# slave_interface.net
KiCad netlist of a schematic drawn in Altium Designer
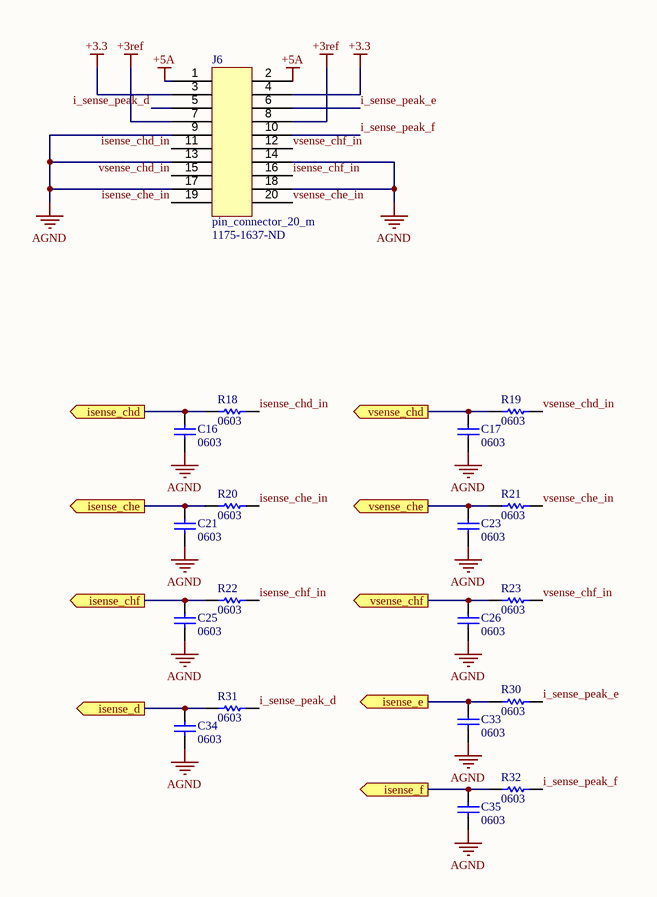
[diagram p0: slave_interface.SchDoc]

(export (version "E")
  (design (tool "Eeschema 10.0.6"))
  (components
    (comp (ref "C16")
      (value "0603")
      (footprint "CAP 0603_1608")
      (description "Capacitor")
      (fields (field (name "PUBLISHER") "Altium Limited"))
      (libsource (lib "Miscellaneous Devices") (part "Cap"))
    )
    (comp (ref "C17")
      (value "0603")
      (footprint "CAP 0603_1608")
      (description "Capacitor")
      (fields (field (name "PUBLISHER") "Altium Limited"))
      (libsource (lib "Miscellaneous Devices") (part "Cap"))
    )
    (comp (ref "C21")
      (value "0603")
      (footprint "CAP 0603_1608")
      (description "Capacitor")
      (fields (field (name "PUBLISHER") "Altium Limited"))
      (libsource (lib "Miscellaneous Devices") (part "Cap"))
    )
    (comp (ref "C23")
      (value "0603")
      (footprint "CAP 0603_1608")
      (description "Capacitor")
      (fields (field (name "PUBLISHER") "Altium Limited"))
      (libsource (lib "Miscellaneous Devices") (part "Cap"))
    )
    (comp (ref "C25")
      (value "0603")
      (footprint "CAP 0603_1608")
      (description "Capacitor")
      (fields (field (name "PUBLISHER") "Altium Limited"))
      (libsource (lib "Miscellaneous Devices") (part "Cap"))
    )
    (comp (ref "C26")
      (value "0603")
      (footprint "CAP 0603_1608")
      (description "Capacitor")
      (fields (field (name "PUBLISHER") "Altium Limited"))
      (libsource (lib "Miscellaneous Devices") (part "Cap"))
    )
    (comp (ref "C33")
      (value "0603")
      (footprint "CAP 0603_1608")
      (description "Capacitor")
      (fields (field (name "PUBLISHER") "Altium Limited"))
      (libsource (lib "Miscellaneous Devices") (part "Cap"))
    )
    (comp (ref "C34")
      (value "0603")
      (footprint "CAP 0603_1608")
      (description "Capacitor")
      (fields (field (name "PUBLISHER") "Altium Limited"))
      (libsource (lib "Miscellaneous Devices") (part "Cap"))
    )
    (comp (ref "C35")
      (value "0603")
      (footprint "CAP 0603_1608")
      (description "Capacitor")
      (fields (field (name "PUBLISHER") "Altium Limited"))
      (libsource (lib "Miscellaneous Devices") (part "Cap"))
    )
    (comp (ref "J6")
      (value "pin_connector_20_m")
      (footprint "PIN_20_MALE_3220-20-0300-00")
      (fields (field (name "SUPPLIER PART NUMBER 1") "1175-1637-ND"))
      (libsource (lib "coil_driver_lib") (part "pin_connector_20_m"))
    )
    (comp (ref "R18")
      (value "0603")
      (footprint "RES 0603_1608")
      (description "Resistor")
      (fields (field (name "PUBLISHER") "Altium Limited"))
      (libsource (lib "Miscellaneous Devices") (part "Res1"))
    )
    (comp (ref "R19")
      (value "0603")
      (footprint "RES 0603_1608")
      (description "Resistor")
      (fields (field (name "PUBLISHER") "Altium Limited"))
      (libsource (lib "Miscellaneous Devices") (part "Res1"))
    )
    (comp (ref "R20")
      (value "0603")
      (footprint "RES 0603_1608")
      (description "Resistor")
      (fields (field (name "PUBLISHER") "Altium Limited"))
      (libsource (lib "Miscellaneous Devices") (part "Res1"))
    )
    (comp (ref "R21")
      (value "0603")
      (footprint "RES 0603_1608")
      (description "Resistor")
      (fields (field (name "PUBLISHER") "Altium Limited"))
      (libsource (lib "Miscellaneous Devices") (part "Res1"))
    )
    (comp (ref "R22")
      (value "0603")
      (footprint "RES 0603_1608")
      (description "Resistor")
      (fields (field (name "PUBLISHER") "Altium Limited"))
      (libsource (lib "Miscellaneous Devices") (part "Res1"))
    )
    (comp (ref "R23")
      (value "0603")
      (footprint "RES 0603_1608")
      (description "Resistor")
      (fields (field (name "PUBLISHER") "Altium Limited"))
      (libsource (lib "Miscellaneous Devices") (part "Res1"))
    )
    (comp (ref "R30")
      (value "0603")
      (footprint "RES 0603_1608")
      (description "Resistor")
      (fields (field (name "PUBLISHER") "Altium Limited"))
      (libsource (lib "Miscellaneous Devices") (part "Res1"))
    )
    (comp (ref "R31")
      (value "0603")
      (footprint "RES 0603_1608")
      (description "Resistor")
      (fields (field (name "PUBLISHER") "Altium Limited"))
      (libsource (lib "Miscellaneous Devices") (part "Res1"))
    )
    (comp (ref "R32")
      (value "0603")
      (footprint "RES 0603_1608")
      (description "Resistor")
      (fields (field (name "PUBLISHER") "Altium Limited"))
      (libsource (lib "Miscellaneous Devices") (part "Res1"))
    )
  )
  (nets
    (net (code "1") (name "+3.3") (class "Default")
      (node (ref "J6") (pin "3") (pintype "passive"))
      (node (ref "J6") (pin "4") (pintype "passive"))
    )
    (net (code "2") (name "+3ref") (class "Default")
      (node (ref "J6") (pin "7") (pintype "passive"))
      (node (ref "J6") (pin "8") (pintype "passive"))
    )
    (net (code "3") (name "+5A") (class "Default")
      (node (ref "J6") (pin "1") (pintype "passive"))
      (node (ref "J6") (pin "2") (pintype "passive"))
    )
    (net (code "4") (name "/i_sense_peak_d") (class "Default")
      (node (ref "J6") (pin "5") (pintype "passive"))
      (node (ref "R31") (pin "2") (pinfunction "2_2") (pintype "passive"))
    )
    (net (code "5") (name "/i_sense_peak_e") (class "Default")
      (node (ref "J6") (pin "6") (pintype "passive"))
      (node (ref "R30") (pin "2") (pinfunction "2_2") (pintype "passive"))
    )
    (net (code "6") (name "/i_sense_peak_f") (class "Default")
      (node (ref "J6") (pin "10") (pintype "passive"))
      (node (ref "R32") (pin "2") (pinfunction "2_2") (pintype "passive"))
    )
    (net (code "7") (name "/isense_chd") (class "Default")
      (node (ref "C16") (pin "2") (pinfunction "2_2") (pintype "passive"))
      (node (ref "R18") (pin "1") (pinfunction "1_1") (pintype "passive"))
    )
    (net (code "8") (name "/isense_chd_in") (class "Default")
      (node (ref "J6") (pin "11") (pintype "passive"))
      (node (ref "R18") (pin "2") (pinfunction "2_2") (pintype "passive"))
    )
    (net (code "9") (name "/isense_che") (class "Default")
      (node (ref "C21") (pin "2") (pinfunction "2_2") (pintype "passive"))
      (node (ref "R20") (pin "1") (pinfunction "1_1") (pintype "passive"))
    )
    (net (code "10") (name "/isense_che_in") (class "Default")
      (node (ref "J6") (pin "19") (pintype "passive"))
      (node (ref "R20") (pin "2") (pinfunction "2_2") (pintype "passive"))
    )
    (net (code "11") (name "/isense_chf") (class "Default")
      (node (ref "C25") (pin "2") (pinfunction "2_2") (pintype "passive"))
      (node (ref "R22") (pin "1") (pinfunction "1_1") (pintype "passive"))
    )
    (net (code "12") (name "/isense_chf_in") (class "Default")
      (node (ref "J6") (pin "16") (pintype "passive"))
      (node (ref "R22") (pin "2") (pinfunction "2_2") (pintype "passive"))
    )
    (net (code "13") (name "/isense_d") (class "Default")
      (node (ref "C34") (pin "2") (pinfunction "2_2") (pintype "passive"))
      (node (ref "R31") (pin "1") (pinfunction "1_1") (pintype "passive"))
    )
    (net (code "14") (name "/isense_e") (class "Default")
      (node (ref "C33") (pin "2") (pinfunction "2_2") (pintype "passive"))
      (node (ref "R30") (pin "1") (pinfunction "1_1") (pintype "passive"))
    )
    (net (code "15") (name "/isense_f") (class "Default")
      (node (ref "C35") (pin "2") (pinfunction "2_2") (pintype "passive"))
      (node (ref "R32") (pin "1") (pinfunction "1_1") (pintype "passive"))
    )
    (net (code "16") (name "/vsense_chd") (class "Default")
      (node (ref "C17") (pin "2") (pinfunction "2_2") (pintype "passive"))
      (node (ref "R19") (pin "1") (pinfunction "1_1") (pintype "passive"))
    )
    (net (code "17") (name "/vsense_chd_in") (class "Default")
      (node (ref "J6") (pin "15") (pintype "passive"))
      (node (ref "R19") (pin "2") (pinfunction "2_2") (pintype "passive"))
    )
    (net (code "18") (name "/vsense_che") (class "Default")
      (node (ref "C23") (pin "2") (pinfunction "2_2") (pintype "passive"))
      (node (ref "R21") (pin "1") (pinfunction "1_1") (pintype "passive"))
    )
    (net (code "19") (name "/vsense_che_in") (class "Default")
      (node (ref "J6") (pin "20") (pintype "passive"))
      (node (ref "R21") (pin "2") (pinfunction "2_2") (pintype "passive"))
    )
    (net (code "20") (name "/vsense_chf") (class "Default")
      (node (ref "C26") (pin "2") (pinfunction "2_2") (pintype "passive"))
      (node (ref "R23") (pin "1") (pinfunction "1_1") (pintype "passive"))
    )
    (net (code "21") (name "/vsense_chf_in") (class "Default")
      (node (ref "J6") (pin "12") (pintype "passive"))
      (node (ref "R23") (pin "2") (pinfunction "2_2") (pintype "passive"))
    )
    (net (code "22") (name "AGND") (class "Default")
      (node (ref "C16") (pin "1") (pinfunction "1_1") (pintype "passive"))
      (node (ref "C17") (pin "1") (pinfunction "1_1") (pintype "passive"))
      (node (ref "C21") (pin "1") (pinfunction "1_1") (pintype "passive"))
      (node (ref "C23") (pin "1") (pinfunction "1_1") (pintype "passive"))
      (node (ref "C25") (pin "1") (pinfunction "1_1") (pintype "passive"))
      (node (ref "C26") (pin "1") (pinfunction "1_1") (pintype "passive"))
      (node (ref "C33") (pin "1") (pinfunction "1_1") (pintype "passive"))
      (node (ref "C34") (pin "1") (pinfunction "1_1") (pintype "passive"))
      (node (ref "C35") (pin "1") (pinfunction "1_1") (pintype "passive"))
      (node (ref "J6") (pin "13") (pintype "passive"))
      (node (ref "J6") (pin "14") (pintype "passive"))
      (node (ref "J6") (pin "17") (pintype "passive"))
      (node (ref "J6") (pin "18") (pintype "passive"))
      (node (ref "J6") (pin "9") (pintype "passive"))
    )
  )
)
